# 13-Experimental.net
KiCad netlist of a schematic drawn in Altium Designer
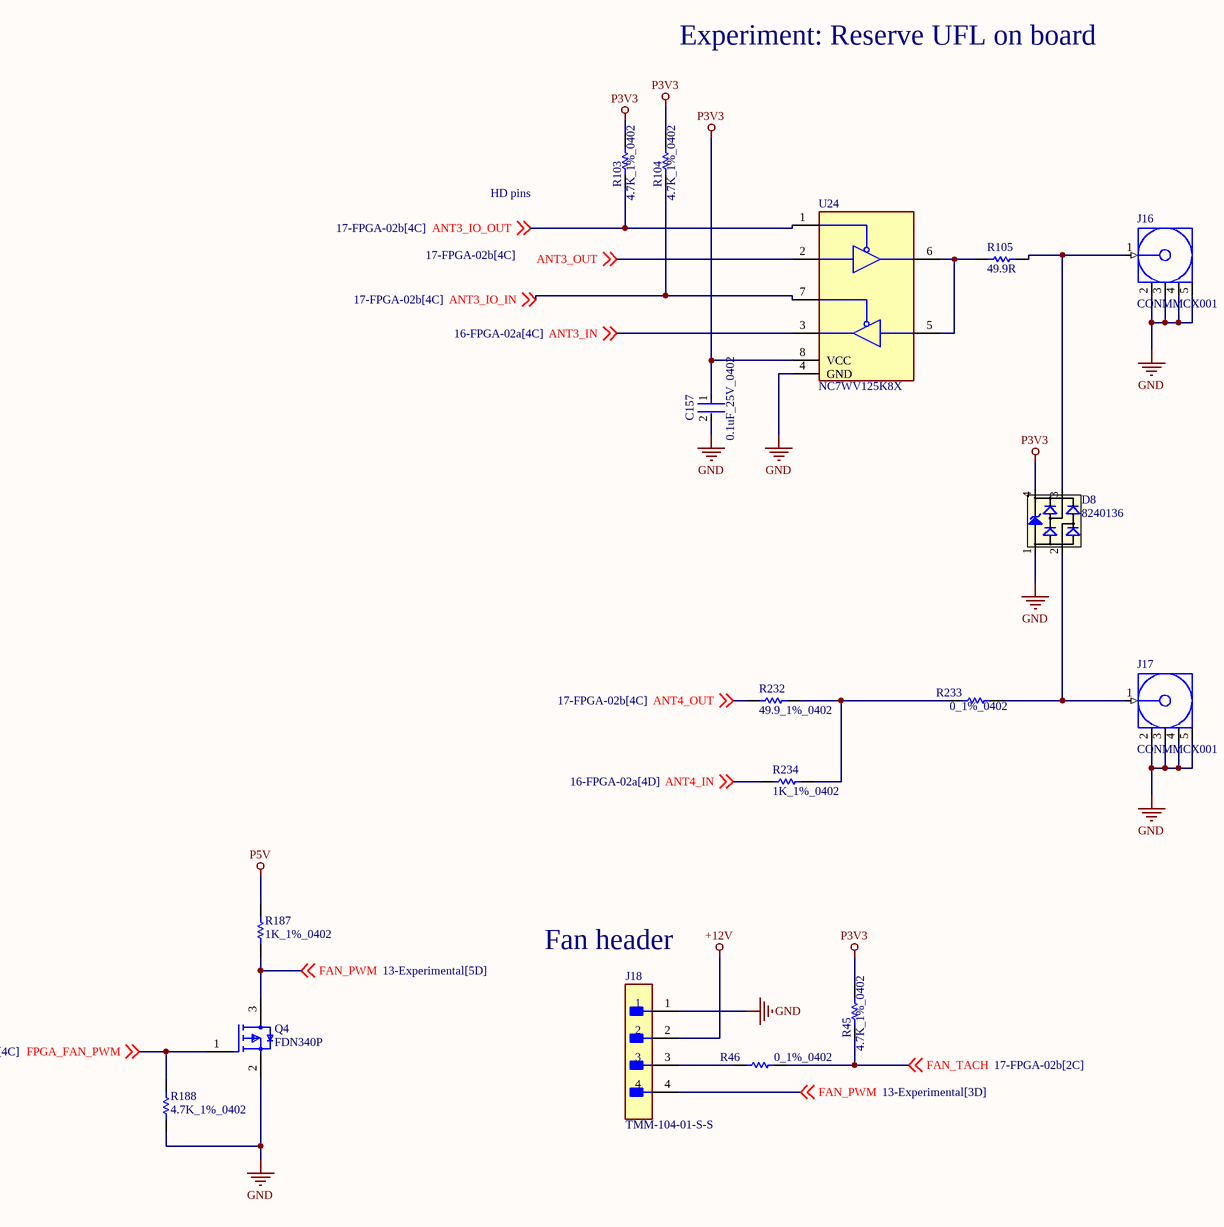
[diagram p0: 13-Experimental.SchDoc]

(export (version "E")
  (design (tool "Eeschema 10.0.6"))
  (components
    (comp (ref "C157")
      (value "0.1uF_25V_0402")
      (footprint "FP-0402-L_1_0_1-W_0_5_0_1-IPC_C")
      (description "General Purpose Ceramic Capacitor, 0402, 100nF, 10%, X7R, 15%, 25V")
      (fields (field (name "VOLTAGE") "25V") (field (name "TOLERANCE") "10%"))
      (libsource (lib "Altium Content Vault") (part "b4654b650e69147ec39a6b967a45e02"))
    )
    (comp (ref "D8")
      (value "8240136")
      (footprint "SOT143-4L")
      (description "TVS Diode WE-TVS-HS, VRWM=3.3V")
      (fields (field (name "MANUFACTURER") "Wuerth Elektronik"))
      (libsource (lib "Altium Content Vault") (part "WE-TVS-HS-4"))
    )
    (comp (ref "J16")
      (value "CONMMCX001")
      (footprint "CON-MMCX")
      (description "MMCX Female PCB Mount Connector, Thru-Hole")
      (libsource (lib "Altium Content Vault") (part "CN-1P-F-RF5"))
    )
    (comp (ref "J17")
      (value "CONMMCX001")
      (footprint "CON-MMCX")
      (description "MMCX Female PCB Mount Connector, Thru-Hole")
      (libsource (lib "Altium Content Vault") (part "CN-1P-F-RF5"))
    )
    (comp (ref "J18")
      (value "TMM-104-01-S-S")
      (footprint "FP-TMM-104-01-S-S-MFG")
      (description "CONN HEADER VERT 4POS 2MM")
      (libsource (lib "Altium Content Vault") (part "299a8cea1bdcbc3624fe62c390fa72c"))
    )
    (comp (ref "Q4")
      (value "FDN340P")
      (footprint "FP-527AG-MFG")
      (description "MOSFET P-CH 20V 2A SSOT3")
      (libsource (lib "Altium Content Vault") (part "d23f43cc42f60b967b7caccf14518fd"))
    )
    (comp (ref "R45")
      (value "4.7K_1%_0402")
      (footprint "RESC1005X40X25NL10T10")
      (fields (field (name "MANUFACTURER") "Bourns") (field (name "PART NUMBER") "CR0402-FX-4701GLF"))
      (libsource (lib "Altium Content Vault") (part "RES"))
    )
    (comp (ref "R46")
      (value "0_1%_0402")
      (footprint "RESC1005X40X25LL05T05")
      (description "Chip Resistor, 0 Ohm, 0.1 W, -55 to 155 degC, 0402 (1005 Metric), RoHS, Tape and Reel")
      (fields (field (name "MANUFACTURER") "Panasonic") (field (name "TOLERANCE") "5%"))
      (libsource (lib "Altium Content Vault") (part "RES-2"))
    )
    (comp (ref "R103")
      (value "4.7K_1%_0402")
      (footprint "RESC1005X40X25NL10T10")
      (fields (field (name "MANUFACTURER") "Bourns") (field (name "PART NUMBER") "CR0402-FX-4701GLF"))
      (libsource (lib "Altium Content Vault") (part "RES"))
    )
    (comp (ref "R104")
      (value "4.7K_1%_0402")
      (footprint "RESC1005X40X25NL10T10")
      (fields (field (name "MANUFACTURER") "Bourns") (field (name "PART NUMBER") "CR0402-FX-4701GLF"))
      (libsource (lib "Altium Content Vault") (part "RES"))
    )
    (comp (ref "R105")
      (value "49.9R")
      (footprint "RESC1608X55X25NL10T15")
      (libsource (lib "Altium Content Vault") (part "RES-2"))
    )
    (comp (ref "R187")
      (value "1K_1%_0402")
      (footprint "RESC1005X40X25NL05T05")
      (fields (field (name "MANUFACTURER") "Vishay Dale") (field (name "PART NUMBER") "CRCW04021K00FKTD"))
      (libsource (lib "Altium Content Vault") (part "RES"))
    )
    (comp (ref "R188")
      (value "4.7K_1%_0402")
      (footprint "RESC1005X40X25NL10T10")
      (fields (field (name "MANUFACTURER") "Bourns") (field (name "PART NUMBER") "CR0402-FX-4701GLF"))
      (libsource (lib "Altium Content Vault") (part "RES"))
    )
    (comp (ref "R232")
      (value "49.9_1%_0402")
      (footprint "RESC1005X40X25NL10T10")
      (fields (field (name "PART NUMBER") "RK73H1ETTP49R9F") (field (name "MANUFACTURER") "KOA Speer"))
      (libsource (lib "Altium Content Vault") (part "RES"))
    )
    (comp (ref "R233")
      (value "0_1%_0402")
      (footprint "RESC1005X40X25LL05T05")
      (description "Chip Resistor, 0 Ohm, 0.1 W, -55 to 155 degC, 0402 (1005 Metric), RoHS, Tape and Reel")
      (fields (field (name "MANUFACTURER") "Panasonic") (field (name "TOLERANCE") "5%"))
      (libsource (lib "Altium Content Vault") (part "RES-2"))
    )
    (comp (ref "R234")
      (value "1K_1%_0402")
      (footprint "RESC1005X40X25NL05T05")
      (fields (field (name "MANUFACTURER") "Vishay Dale") (field (name "PART NUMBER") "CRCW04021K00FKTD"))
      (libsource (lib "Altium Content Vault") (part "RES"))
    )
    (comp (ref "U24")
      (value "NC7WV125K8X")
      (footprint "SOP50P310X90-8N")
      (description "Integrated Circuit")
      (fields (field (name "MOUSER PART NUMBER") "512-NC7WV125K8X"))
      (libsource (lib "SamacSys") (part "NC7WV125K8X"))
    )
  )
  (nets
    (net (code "1") (name "+12V") (class "Default")
      (node (ref "J18") (pin "2") (pinfunction "2_2") (pintype "passive"))
    )
    (net (code "2") (name "ANT3_IN") (class "Default") (node (ref "U24") (pin "3") (pintype "passive")))
    (net (code "3") (name "ANT3_IO_IN") (class "Default")
      (node (ref "R104") (pin "2") (pinfunction "2_2") (pintype "passive"))
      (node (ref "U24") (pin "7") (pintype "passive"))
    )
    (net (code "4") (name "ANT3_IO_OUT") (class "Default")
      (node (ref "R103") (pin "2") (pinfunction "2_2") (pintype "passive"))
      (node (ref "U24") (pin "1") (pintype "passive"))
    )
    (net (code "5") (name "ANT3_OUT") (class "Default") (node (ref "U24") (pin "2") (pintype "passive")))
    (net (code "6") (name "ANT4_IN") (class "Default")
      (node (ref "R234") (pin "1") (pinfunction "1_1") (pintype "passive"))
    )
    (net (code "7") (name "ANT4_OUT") (class "Default")
      (node (ref "R232") (pin "1") (pinfunction "1_1") (pintype "passive"))
    )
    (net (code "8") (name "FAN_PWM") (class "Default")
      (node (ref "J18") (pin "4") (pinfunction "4_4") (pintype "passive"))
      (node (ref "Q4") (pin "3") (pinfunction "D_3") (pintype "passive"))
      (node (ref "R187") (pin "1") (pinfunction "1_1") (pintype "passive"))
    )
    (net (code "9") (name "FAN_TACH") (class "Default")
      (node (ref "R45") (pin "2") (pinfunction "2_2") (pintype "passive"))
      (node (ref "R46") (pin "2") (pinfunction "2_2") (pintype "passive"))
    )
    (net (code "10") (name "FPGA_FAN_PWM") (class "Default")
      (node (ref "Q4") (pin "1") (pinfunction "G_1") (pintype "passive"))
      (node (ref "R188") (pin "2") (pinfunction "2_2") (pintype "passive"))
    )
    (net (code "11") (name "GND") (class "Default")
      (node (ref "C157") (pin "2") (pinfunction "2_2") (pintype "passive"))
      (node (ref "D8") (pin "1") (pinfunction "GND_1") (pintype "passive"))
      (node (ref "J16") (pin "2") (pinfunction "GND_2") (pintype "power_in"))
      (node (ref "J16") (pin "3") (pinfunction "GND_3") (pintype "power_in"))
      (node (ref "J16") (pin "4") (pinfunction "GND_4") (pintype "power_in"))
      (node (ref "J16") (pin "5") (pinfunction "GND_5") (pintype "power_in"))
      (node (ref "J17") (pin "2") (pinfunction "GND_2") (pintype "power_in"))
      (node (ref "J17") (pin "3") (pinfunction "GND_3") (pintype "power_in"))
      (node (ref "J17") (pin "4") (pinfunction "GND_4") (pintype "power_in"))
      (node (ref "J17") (pin "5") (pinfunction "GND_5") (pintype "power_in"))
      (node (ref "J18") (pin "1") (pinfunction "1_1") (pintype "passive"))
      (node (ref "Q4") (pin "2") (pinfunction "S_2") (pintype "passive"))
      (node (ref "R188") (pin "1") (pinfunction "1_1") (pintype "passive"))
      (node (ref "U24") (pin "4") (pinfunction "GND_4") (pintype "passive"))
    )
    (net (code "12") (name "Net-(D8-I{slash}O1)") (class "Default")
      (node (ref "D8") (pin "2") (pinfunction "I/O1_2") (pintype "passive"))
      (node (ref "J17") (pin "1") (pinfunction "Signal_1") (pintype "input"))
      (node (ref "R233") (pin "2") (pinfunction "2_2") (pintype "passive"))
    )
    (net (code "13") (name "Net-(D8-I{slash}O2)") (class "Default")
      (node (ref "D8") (pin "3") (pinfunction "I/O2_3") (pintype "passive"))
      (node (ref "J16") (pin "1") (pinfunction "Signal_1") (pintype "input"))
      (node (ref "R105") (pin "2") (pinfunction "2_2") (pintype "passive"))
    )
    (net (code "14") (name "Net-(J18-Pad3)") (class "Default")
      (node (ref "J18") (pin "3") (pinfunction "3_3") (pintype "passive"))
      (node (ref "R46") (pin "1") (pinfunction "1_1") (pintype "passive"))
    )
    (net (code "15") (name "Net-(R105-Pad1)") (class "Default")
      (node (ref "R105") (pin "1") (pinfunction "1_1") (pintype "passive"))
      (node (ref "U24") (pin "5") (pintype "passive"))
      (node (ref "U24") (pin "6") (pintype "passive"))
    )
    (net (code "16") (name "Net-(R232-Pad2)") (class "Default")
      (node (ref "R232") (pin "2") (pinfunction "2_2") (pintype "passive"))
      (node (ref "R233") (pin "1") (pinfunction "1_1") (pintype "passive"))
      (node (ref "R234") (pin "2") (pinfunction "2_2") (pintype "passive"))
    )
    (net (code "17") (name "P3V3") (class "Default")
      (node (ref "C157") (pin "1") (pinfunction "1_1") (pintype "passive"))
      (node (ref "D8") (pin "4") (pinfunction "VDD_4") (pintype "passive"))
      (node (ref "R103") (pin "1") (pinfunction "1_1") (pintype "passive"))
      (node (ref "R104") (pin "1") (pinfunction "1_1") (pintype "passive"))
      (node (ref "R45") (pin "1") (pinfunction "1_1") (pintype "passive"))
      (node (ref "U24") (pin "8") (pinfunction "VCC_8") (pintype "passive"))
    )
    (net (code "18") (name "P5V") (class "Default")
      (node (ref "R187") (pin "2") (pinfunction "2_2") (pintype "passive"))
    )
  )
)
